# microcontroleur.net
KiCad netlist of a schematic drawn in Altium Designer
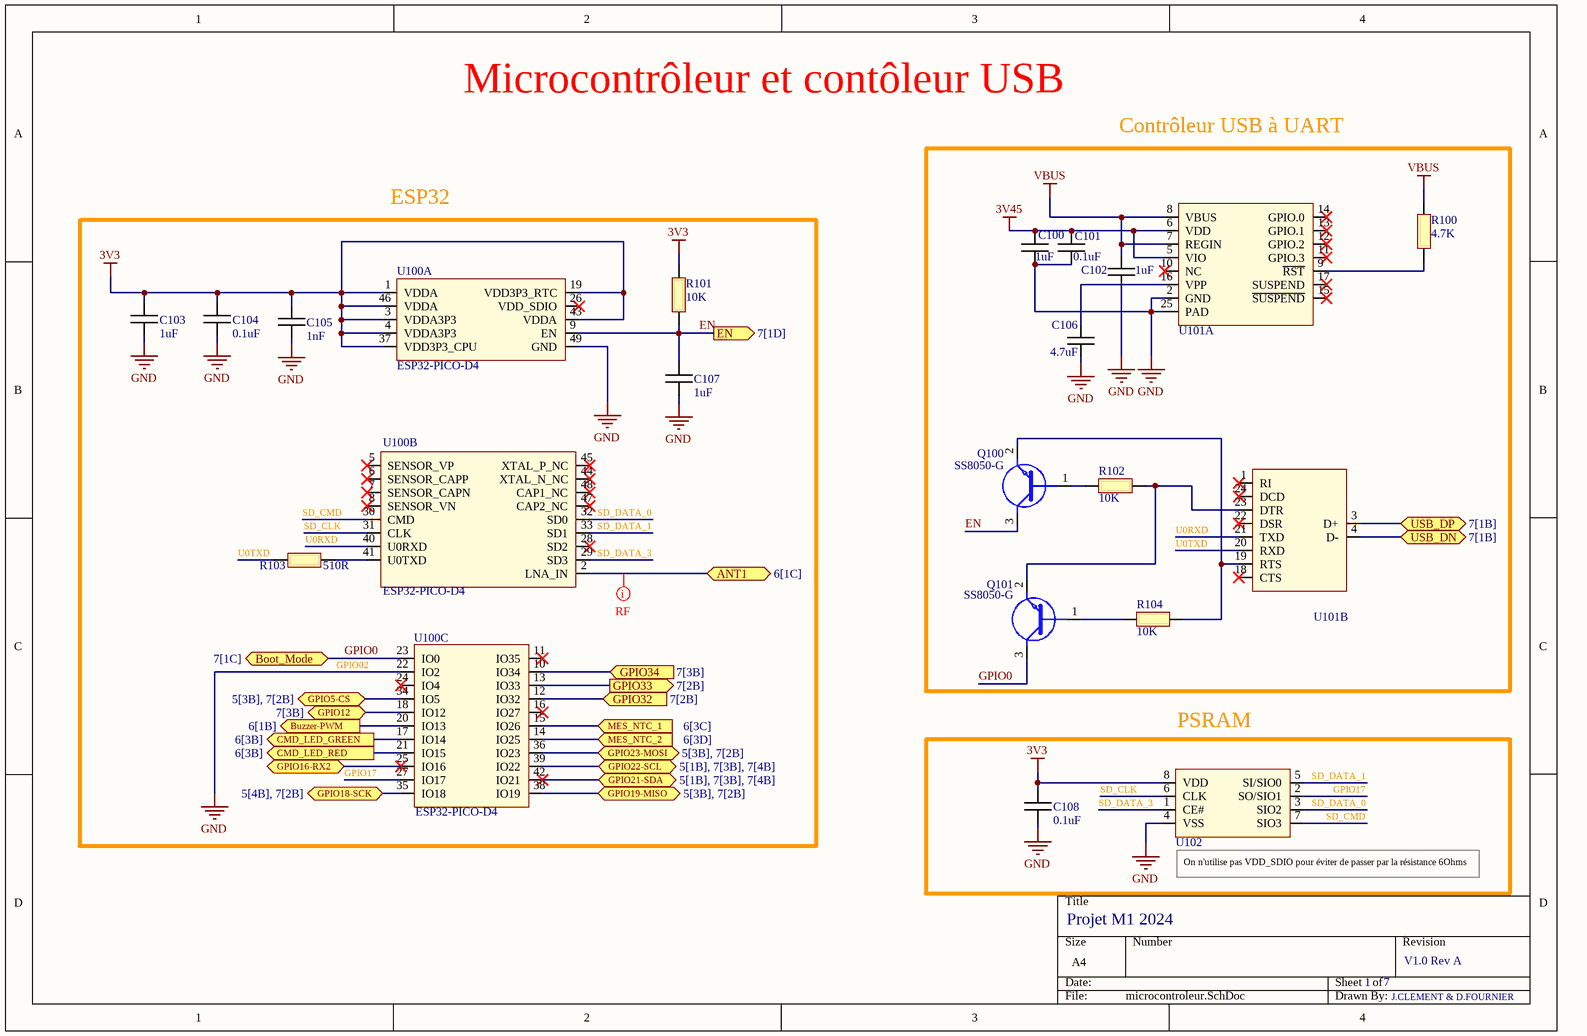
[diagram p0: microcontroleur.SchDoc]

(export (version "E")
  (design (tool "Eeschema 10.0.6"))
  (components
    (comp (ref "C100")
      (value "1uF")
      (footprint "CAPA_0603")
      (libsource (lib "SCHLibrary") (part "Capacitor"))
    )
    (comp (ref "C101")
      (value "0.1uF")
      (footprint "CAPA_0603")
      (libsource (lib "SCHLibrary") (part "Capacitor"))
    )
    (comp (ref "C102")
      (value "1uF")
      (footprint "CAPA_0603")
      (libsource (lib "SCHLibrary") (part "Capacitor"))
    )
    (comp (ref "C103")
      (value "1uF")
      (footprint "CAPA_0603")
      (libsource (lib "SCHLibrary") (part "Capacitor"))
    )
    (comp (ref "C104")
      (value "0.1uF")
      (footprint "CAPA_0603")
      (libsource (lib "SCHLibrary") (part "Capacitor"))
    )
    (comp (ref "C105")
      (value "1nF")
      (footprint "CAPA_0603")
      (libsource (lib "SCHLibrary") (part "Capacitor"))
    )
    (comp (ref "C106")
      (value "4.7uF")
      (footprint "CAPA_0603")
      (libsource (lib "SCHLibrary") (part "Capacitor"))
    )
    (comp (ref "C107")
      (value "1uF")
      (footprint "CAPA_0603")
      (libsource (lib "SCHLibrary") (part "Capacitor"))
    )
    (comp (ref "C108")
      (value "0.1uF")
      (footprint "CAPA_0603")
      (libsource (lib "SCHLibrary") (part "Capacitor"))
    )
    (comp (ref "Q100")
      (value "SS8050-G")
      (footprint "SS8050-G")
      (description "Bipolar Transistors - BJT NPN TRANSISTOR 1.5A 40V")
      (libsource (lib "SCHLibrary") (part "SS8050-G"))
    )
    (comp (ref "Q101")
      (value "SS8050-G")
      (footprint "SS8050-G")
      (description "Bipolar Transistors - BJT NPN TRANSISTOR 1.5A 40V")
      (libsource (lib "SCHLibrary") (part "SS8050-G"))
    )
    (comp (ref "R100") (value "4.7K") (footprint "RES_0603") (libsource (lib "SCHLibrary") (part "Resistor")))
    (comp (ref "R101") (value "10K") (footprint "RES_0603") (libsource (lib "SCHLibrary") (part "Resistor")))
    (comp (ref "R102") (value "10K") (footprint "RES_0603") (libsource (lib "") (part "Resistor_1")))
    (comp (ref "R103") (value "510R") (footprint "RES_0603") (libsource (lib "") (part "Resistor_1")))
    (comp (ref "R104") (value "10K") (footprint "RES_0603") (libsource (lib "") (part "Resistor_1")))
    (comp (ref "U100")
      (value "ESP32-PICO-D4")
      (footprint "PQFN50P700X700X104_HS-49N")
      (libsource (lib "SCHLibrary") (part "ESP32"))
    )
    (comp (ref "U101")
      (value "CP2104-F03-GM")
      (footprint "PQFN50P400X400X80_HS-25N")
      (description "USB Bridge, USB to UART USB 2.0 UART Interface 24-QFN (4x4)")
      (libsource (lib "SCHLibrary") (part "USBBridge"))
    )
    (comp (ref "U102")
      (value "IS66WVS1M8BLL-104NLI")
      (footprint "SOIC127P600X175-8N")
      (description "SRAM 8Mb, SerialRAM, 2.7V-3.6V, 104MHz, 8 pin SOIC 150 mil, RoHS")
      (libsource (lib "SCHLibrary") (part "SRAM"))
    )
  )
  (nets
    (net (code "1") (name "/ANT1") (class "Default")
      (node (ref "U100") (pin "2") (pinfunction "LNA_IN_2") (pintype "passive"))
    )
    (net (code "2") (name "/Buzzer-PWM") (class "Default")
      (node (ref "U100") (pin "20") (pinfunction "IO13_20") (pintype "passive"))
    )
    (net (code "3") (name "/CMD_LED_GREEN") (class "Default")
      (node (ref "U100") (pin "17") (pinfunction "IO14_17") (pintype "passive"))
    )
    (net (code "4") (name "/CMD_LED_RED") (class "Default")
      (node (ref "U100") (pin "21") (pinfunction "IO15_21") (pintype "passive"))
    )
    (net (code "5") (name "/EN") (class "Default")
      (node (ref "C107") (pin "1") (pinfunction "1_1") (pintype "passive"))
      (node (ref "Q100") (pin "3") (pinfunction "C_3") (pintype "passive"))
      (node (ref "R101") (pin "1") (pinfunction "1_1") (pintype "passive"))
      (node (ref "U100") (pin "9") (pinfunction "EN_9") (pintype "passive"))
    )
    (net (code "6") (name "/GPIO0") (class "Default")
      (node (ref "Q101") (pin "3") (pinfunction "C_3") (pintype "passive"))
      (node (ref "U100") (pin "23") (pinfunction "IO0_23") (pintype "passive"))
    )
    (net (code "7") (name "/GPIO5-CS") (class "Default")
      (node (ref "U100") (pin "34") (pinfunction "IO5_34") (pintype "passive"))
    )
    (net (code "8") (name "/GPIO12") (class "Default")
      (node (ref "U100") (pin "18") (pinfunction "IO12_18") (pintype "passive"))
    )
    (net (code "9") (name "/GPIO16-RX2") (class "Default")
      (node (ref "U100") (pin "25") (pinfunction "IO16_25") (pintype "passive+no_connect"))
    )
    (net (code "10") (name "/GPIO17") (class "Default")
      (node (ref "U100") (pin "27") (pinfunction "IO17_27") (pintype "passive"))
      (node (ref "U102") (pin "2") (pinfunction "SO/SIO1_2") (pintype "passive"))
    )
    (net (code "11") (name "/GPIO18-SCK") (class "Default")
      (node (ref "U100") (pin "35") (pinfunction "IO18_35") (pintype "passive"))
    )
    (net (code "12") (name "/GPIO19-MISO") (class "Default")
      (node (ref "U100") (pin "38") (pinfunction "IO19_38") (pintype "passive"))
    )
    (net (code "13") (name "/GPIO21-SDA") (class "Default")
      (node (ref "U100") (pin "42") (pinfunction "IO21_42") (pintype "passive+no_connect"))
    )
    (net (code "14") (name "/GPIO22-SCL") (class "Default")
      (node (ref "U100") (pin "39") (pinfunction "IO22_39") (pintype "passive"))
    )
    (net (code "15") (name "/GPIO23-MOSI") (class "Default")
      (node (ref "U100") (pin "36") (pinfunction "IO23_36") (pintype "passive"))
    )
    (net (code "16") (name "/GPIO32") (class "Default")
      (node (ref "U100") (pin "12") (pinfunction "IO32_12") (pintype "passive"))
    )
    (net (code "17") (name "/GPIO33") (class "Default")
      (node (ref "U100") (pin "13") (pinfunction "IO33_13") (pintype "passive"))
    )
    (net (code "18") (name "/GPIO34") (class "Default")
      (node (ref "U100") (pin "10") (pinfunction "IO34_10") (pintype "passive"))
    )
    (net (code "19") (name "/MES_NTC_1") (class "Default")
      (node (ref "U100") (pin "15") (pinfunction "IO26_15") (pintype "passive"))
    )
    (net (code "20") (name "/MES_NTC_2") (class "Default")
      (node (ref "U100") (pin "14") (pinfunction "IO25_14") (pintype "passive"))
    )
    (net (code "21") (name "/SD_CLK") (class "Default")
      (node (ref "U100") (pin "31") (pinfunction "CLK_31") (pintype "passive"))
      (node (ref "U102") (pin "6") (pinfunction "CLK_6") (pintype "passive"))
    )
    (net (code "22") (name "/SD_CMD") (class "Default")
      (node (ref "U100") (pin "30") (pinfunction "CMD_30") (pintype "passive"))
      (node (ref "U102") (pin "7") (pinfunction "SIO3_7") (pintype "passive"))
    )
    (net (code "23") (name "/SD_DATA_0") (class "Default")
      (node (ref "U100") (pin "32") (pinfunction "SD0_32") (pintype "passive"))
      (node (ref "U102") (pin "3") (pinfunction "SIO2_3") (pintype "passive"))
    )
    (net (code "24") (name "/SD_DATA_1") (class "Default")
      (node (ref "U100") (pin "33") (pinfunction "SD1_33") (pintype "passive"))
      (node (ref "U102") (pin "5") (pinfunction "SI/SIO0_5") (pintype "passive"))
    )
    (net (code "25") (name "/SD_DATA_3") (class "Default")
      (node (ref "U100") (pin "29") (pinfunction "SD3_29") (pintype "passive"))
      (node (ref "U102") (pin "1") (pinfunction "CE#_1") (pintype "passive"))
    )
    (net (code "26") (name "/U0RXD") (class "Default")
      (node (ref "U100") (pin "40") (pinfunction "U0RXD_40") (pintype "passive"))
      (node (ref "U101") (pin "21") (pinfunction "TXD_21") (pintype "passive"))
    )
    (net (code "27") (name "/U0TXD") (class "Default")
      (node (ref "R103") (pin "1") (pinfunction "1_1") (pintype "passive"))
      (node (ref "U101") (pin "20") (pinfunction "RXD_20") (pintype "passive"))
    )
    (net (code "28") (name "/USB_DN") (class "Default")
      (node (ref "U101") (pin "4") (pinfunction "D-_4") (pintype "passive"))
    )
    (net (code "29") (name "/USB_DP") (class "Default")
      (node (ref "U101") (pin "3") (pinfunction "D+_3") (pintype "passive"))
    )
    (net (code "30") (name "3V3") (class "Default")
      (node (ref "C103") (pin "1") (pinfunction "1_1") (pintype "passive"))
      (node (ref "C104") (pin "1") (pinfunction "1_1") (pintype "passive"))
      (node (ref "C105") (pin "1") (pinfunction "1_1") (pintype "passive"))
      (node (ref "C108") (pin "1") (pinfunction "1_1") (pintype "passive"))
      (node (ref "R101") (pin "2") (pinfunction "2_2") (pintype "passive"))
      (node (ref "U100") (pin "1") (pinfunction "VDDA_1") (pintype "passive"))
      (node (ref "U100") (pin "19") (pinfunction "VDD3P3_RTC_19") (pintype "passive"))
      (node (ref "U100") (pin "3") (pinfunction "VDDA3P3_3") (pintype "passive"))
      (node (ref "U100") (pin "37") (pinfunction "VDD3P3_CPU_37") (pintype "passive"))
      (node (ref "U100") (pin "4") (pinfunction "VDDA3P3_4") (pintype "passive"))
      (node (ref "U100") (pin "43") (pinfunction "VDDA_43") (pintype "passive"))
      (node (ref "U100") (pin "46") (pinfunction "VDDA_46") (pintype "passive"))
      (node (ref "U102") (pin "8") (pinfunction "VDD_8") (pintype "passive"))
    )
    (net (code "31") (name "3V45") (class "Default")
      (node (ref "C100") (pin "1") (pinfunction "1_1") (pintype "passive"))
      (node (ref "C101") (pin "1") (pinfunction "1_1") (pintype "passive"))
      (node (ref "U101") (pin "5") (pinfunction "VIO_5") (pintype "passive"))
      (node (ref "U101") (pin "6") (pinfunction "VDD_6") (pintype "passive"))
    )
    (net (code "32") (name "GND") (class "Default")
      (node (ref "C100") (pin "2") (pinfunction "2_2") (pintype "passive"))
      (node (ref "C101") (pin "2") (pinfunction "2_2") (pintype "passive"))
      (node (ref "C102") (pin "2") (pinfunction "2_2") (pintype "passive"))
      (node (ref "C103") (pin "2") (pinfunction "2_2") (pintype "passive"))
      (node (ref "C104") (pin "2") (pinfunction "2_2") (pintype "passive"))
      (node (ref "C105") (pin "2") (pinfunction "2_2") (pintype "passive"))
      (node (ref "C106") (pin "2") (pinfunction "2_2") (pintype "passive"))
      (node (ref "C107") (pin "2") (pinfunction "2_2") (pintype "passive"))
      (node (ref "C108") (pin "2") (pinfunction "2_2") (pintype "passive"))
      (node (ref "U100") (pin "22") (pinfunction "IO2_22") (pintype "passive"))
      (node (ref "U100") (pin "49") (pinfunction "GND_49") (pintype "passive"))
      (node (ref "U101") (pin "2") (pinfunction "GND_2") (pintype "passive"))
      (node (ref "U101") (pin "25") (pinfunction "PAD_25") (pintype "passive"))
      (node (ref "U102") (pin "4") (pinfunction "VSS_4") (pintype "passive"))
    )
    (net (code "33") (name "Net-(Q100-B)") (class "Default")
      (node (ref "Q100") (pin "1") (pinfunction "B_1") (pintype "passive"))
      (node (ref "R102") (pin "1") (pinfunction "1_1") (pintype "passive"))
    )
    (net (code "34") (name "Net-(Q100-E)") (class "Default")
      (node (ref "Q100") (pin "2") (pinfunction "E_2") (pintype "passive"))
      (node (ref "R104") (pin "2") (pinfunction "2_2") (pintype "passive"))
      (node (ref "U101") (pin "19") (pinfunction "RTS_19") (pintype "passive"))
    )
    (net (code "35") (name "Net-(Q101-B)") (class "Default")
      (node (ref "Q101") (pin "1") (pinfunction "B_1") (pintype "passive"))
      (node (ref "R104") (pin "1") (pinfunction "1_1") (pintype "passive"))
    )
    (net (code "36") (name "Net-(Q101-E)") (class "Default")
      (node (ref "Q101") (pin "2") (pinfunction "E_2") (pintype "passive"))
      (node (ref "R102") (pin "2") (pinfunction "2_2") (pintype "passive"))
      (node (ref "U101") (pin "23") (pinfunction "DTR_23") (pintype "passive"))
    )
    (net (code "37") (name "Net-(U100B-U0TXD)") (class "Default")
      (node (ref "R103") (pin "2") (pinfunction "2_2") (pintype "passive"))
      (node (ref "U100") (pin "41") (pinfunction "U0TXD_41") (pintype "passive"))
    )
    (net (code "38") (name "Net-(U101A-VPP)") (class "Default")
      (node (ref "C106") (pin "1") (pinfunction "1_1") (pintype "passive"))
      (node (ref "U101") (pin "16") (pinfunction "VPP_16") (pintype "passive"))
    )
    (net (code "39") (name "Net-(U101A-~{RST})") (class "Default")
      (node (ref "R100") (pin "1") (pinfunction "1_1") (pintype "passive"))
      (node (ref "U101") (pin "9") (pinfunction "~{RST}_9") (pintype "passive"))
    )
    (net (code "40") (name "VBUS") (class "Default")
      (node (ref "C102") (pin "1") (pinfunction "1_1") (pintype "passive"))
      (node (ref "R100") (pin "2") (pinfunction "2_2") (pintype "passive"))
      (node (ref "U101") (pin "7") (pinfunction "REGIN_7") (pintype "passive"))
      (node (ref "U101") (pin "8") (pinfunction "VBUS_8") (pintype "passive"))
    )
    (net (code "41") (name "unconnected-(U100A-VDD_SDIO-Pad26)") (class "Default")
      (node (ref "U100") (pin "26") (pinfunction "VDD_SDIO_26") (pintype "passive+no_connect"))
    )
    (net (code "42") (name "unconnected-(U100B-CAP1_NC-Pad48)") (class "Default")
      (node (ref "U100") (pin "48") (pinfunction "CAP1_NC_48") (pintype "passive+no_connect"))
    )
    (net (code "43") (name "unconnected-(U100B-CAP2_NC-Pad47)") (class "Default")
      (node (ref "U100") (pin "47") (pinfunction "CAP2_NC_47") (pintype "passive+no_connect"))
    )
    (net (code "44") (name "unconnected-(U100B-SD2-Pad28)") (class "Default")
      (node (ref "U100") (pin "28") (pinfunction "SD2_28") (pintype "passive+no_connect"))
    )
    (net (code "45") (name "unconnected-(U100B-SENSOR_CAPN-Pad7)") (class "Default")
      (node (ref "U100") (pin "7") (pinfunction "SENSOR_CAPN_7") (pintype "passive+no_connect"))
    )
    (net (code "46") (name "unconnected-(U100B-SENSOR_CAPP-Pad6)") (class "Default")
      (node (ref "U100") (pin "6") (pinfunction "SENSOR_CAPP_6") (pintype "passive+no_connect"))
    )
    (net (code "47") (name "unconnected-(U100B-SENSOR_VN-Pad8)") (class "Default")
      (node (ref "U100") (pin "8") (pinfunction "SENSOR_VN_8") (pintype "passive+no_connect"))
    )
    (net (code "48") (name "unconnected-(U100B-SENSOR_VP-Pad5)") (class "Default")
      (node (ref "U100") (pin "5") (pinfunction "SENSOR_VP_5") (pintype "passive+no_connect"))
    )
    (net (code "49") (name "unconnected-(U100B-XTAL_N_NC-Pad44)") (class "Default")
      (node (ref "U100") (pin "44") (pinfunction "XTAL_N_NC_44") (pintype "passive+no_connect"))
    )
    (net (code "50") (name "unconnected-(U100B-XTAL_P_NC-Pad45)") (class "Default")
      (node (ref "U100") (pin "45") (pinfunction "XTAL_P_NC_45") (pintype "passive+no_connect"))
    )
    (net (code "51") (name "unconnected-(U100C-IO4-Pad24)") (class "Default")
      (node (ref "U100") (pin "24") (pinfunction "IO4_24") (pintype "passive+no_connect"))
    )
    (net (code "52") (name "unconnected-(U100C-IO27-Pad16)") (class "Default")
      (node (ref "U100") (pin "16") (pinfunction "IO27_16") (pintype "passive+no_connect"))
    )
    (net (code "53") (name "unconnected-(U100C-IO35-Pad11)") (class "Default")
      (node (ref "U100") (pin "11") (pinfunction "IO35_11") (pintype "passive+no_connect"))
    )
    (net (code "54") (name "unconnected-(U101A-GPIO.0-Pad14)") (class "Default")
      (node (ref "U101") (pin "14") (pinfunction "GPIO.0_14") (pintype "passive+no_connect"))
    )
    (net (code "55") (name "unconnected-(U101A-GPIO.1-Pad13)") (class "Default")
      (node (ref "U101") (pin "13") (pinfunction "GPIO.1_13") (pintype "passive+no_connect"))
    )
    (net (code "56") (name "unconnected-(U101A-GPIO.2-Pad12)") (class "Default")
      (node (ref "U101") (pin "12") (pinfunction "GPIO.2_12") (pintype "passive+no_connect"))
    )
    (net (code "57") (name "unconnected-(U101A-GPIO.3-Pad11)") (class "Default")
      (node (ref "U101") (pin "11") (pinfunction "GPIO.3_11") (pintype "passive+no_connect"))
    )
    (net (code "58") (name "unconnected-(U101A-NC-Pad10)") (class "Default")
      (node (ref "U101") (pin "10") (pinfunction "NC_10") (pintype "passive+no_connect"))
    )
    (net (code "59") (name "unconnected-(U101A-SUSPEND-Pad17)") (class "Default")
      (node (ref "U101") (pin "17") (pinfunction "SUSPEND_17") (pintype "passive+no_connect"))
    )
    (net (code "60") (name "unconnected-(U101A-~{SUSPEND}-Pad15)") (class "Default")
      (node (ref "U101") (pin "15") (pinfunction "~{SUSPEND}_15") (pintype "passive+no_connect"))
    )
    (net (code "61") (name "unconnected-(U101B-CTS-Pad18)") (class "Default")
      (node (ref "U101") (pin "18") (pinfunction "CTS_18") (pintype "passive+no_connect"))
    )
    (net (code "62") (name "unconnected-(U101B-DCD-Pad24)") (class "Default")
      (node (ref "U101") (pin "24") (pinfunction "DCD_24") (pintype "passive+no_connect"))
    )
    (net (code "63") (name "unconnected-(U101B-DSR-Pad22)") (class "Default")
      (node (ref "U101") (pin "22") (pinfunction "DSR_22") (pintype "passive+no_connect"))
    )
    (net (code "64") (name "unconnected-(U101B-RI-Pad1)") (class "Default")
      (node (ref "U101") (pin "1") (pinfunction "RI_1") (pintype "passive+no_connect"))
    )
  )
)
